# untitled.net
KiCad netlist of a schematic drawn in EAGLE
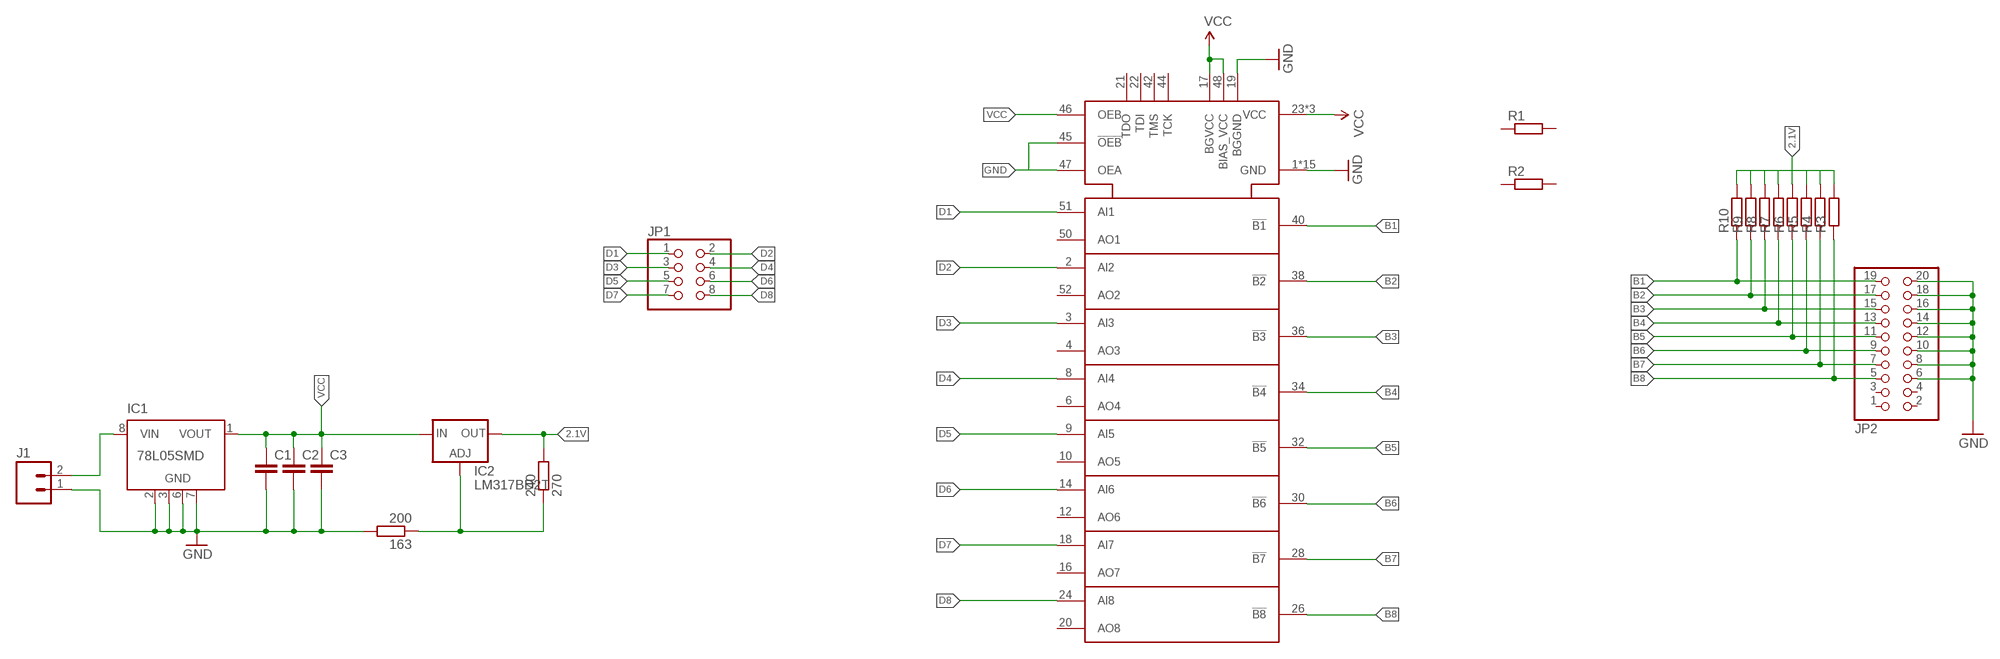
[diagram p0: schematic, sheet 1]

(export (version "E")
  (design (tool "Eeschema 10.0.6"))
  (components
    (comp (ref "163")
      (value "200")
      (footprint "eagle-import:R0805")
      (libsource (lib "eagle-import") (part "R0805"))
    )
    (comp (ref "240")
      (value "270")
      (footprint "eagle-import:R0805")
      (libsource (lib "eagle-import") (part "R0805"))
    )
    (comp (ref "C1")
      (value "CC0805")
      (footprint "eagle-import:C0805")
      (libsource (lib "eagle-import") (part "CC0805"))
    )
    (comp (ref "C2")
      (value "CC0805")
      (footprint "eagle-import:C0805")
      (libsource (lib "eagle-import") (part "CC0805"))
    )
    (comp (ref "C3")
      (value "CC0805")
      (footprint "eagle-import:C0805")
      (libsource (lib "eagle-import") (part "CC0805"))
    )
    (comp (ref "IC1")
      (value "78L05SMD")
      (footprint "eagle-import:SO08")
      (libsource (lib "eagle-import") (part "78LSMD05"))
    )
    (comp (ref "IC2")
      (value "LM317BD2T")
      (footprint "eagle-import:D2PACK")
      (libsource (lib "eagle-import") (part "LM317?BD2T"))
    )
    (comp (ref "J1")
      (value "M02LOCK_LONGPADS")
      (footprint "eagle-import:1X02_LOCK_LONGPADS")
      (libsource (lib "eagle-import") (part "M02LOCK_LONGPADS"))
    )
    (comp (ref "JP1")
      (value "PINHD-2X04_2.54-SMD")
      (footprint "eagle-import:2X04SMD")
      (libsource (lib "eagle-import") (part "PINHD-2X04_2.54-SMD"))
    )
    (comp (ref "JP2")
      (value "PINHD-2X10_2.54-SMD")
      (footprint "eagle-import:2X10SMD")
      (libsource (lib "eagle-import") (part "PINHD-2X10_2.54-SMD"))
    )
    (comp (ref "R1")
      (value "R0805")
      (footprint "eagle-import:R0805")
      (libsource (lib "eagle-import") (part "R0805"))
    )
    (comp (ref "R2")
      (value "R0805")
      (footprint "eagle-import:R0805")
      (libsource (lib "eagle-import") (part "R0805"))
    )
    (comp (ref "R3")
      (value "R0805")
      (footprint "eagle-import:R0805")
      (libsource (lib "eagle-import") (part "R0805"))
    )
    (comp (ref "R4")
      (value "R0805")
      (footprint "eagle-import:R0805")
      (libsource (lib "eagle-import") (part "R0805"))
    )
    (comp (ref "R5")
      (value "R0805")
      (footprint "eagle-import:R0805")
      (libsource (lib "eagle-import") (part "R0805"))
    )
    (comp (ref "R6")
      (value "R0805")
      (footprint "eagle-import:R0805")
      (libsource (lib "eagle-import") (part "R0805"))
    )
    (comp (ref "R7")
      (value "R0805")
      (footprint "eagle-import:R0805")
      (libsource (lib "eagle-import") (part "R0805"))
    )
    (comp (ref "R8")
      (value "R0805")
      (footprint "eagle-import:R0805")
      (libsource (lib "eagle-import") (part "R0805"))
    )
    (comp (ref "R9")
      (value "R0805")
      (footprint "eagle-import:R0805")
      (libsource (lib "eagle-import") (part "R0805"))
    )
    (comp (ref "R10")
      (value "R0805")
      (footprint "eagle-import:R0805")
      (libsource (lib "eagle-import") (part "R0805"))
    )
    (comp (ref "U$1")
      (value "SN74FB2050")
      (footprint "eagle-import:TQFP-10X10-52")
      (libsource (lib "eagle-import") (part "SN74FB2050"))
    )
  )
  (nets
    (net (code "1") (name "2.1V") (class "Default")
      (node (ref "240") (pin "2") (pinfunction "2_2") (pintype "passive"))
      (node (ref "IC2") (pin "2") (pinfunction "OUT_2") (pintype "passive"))
      (node (ref "R10") (pin "2") (pinfunction "2_2") (pintype "passive"))
      (node (ref "R3") (pin "2") (pinfunction "2_2") (pintype "passive"))
      (node (ref "R4") (pin "2") (pinfunction "2_2") (pintype "passive"))
      (node (ref "R5") (pin "2") (pinfunction "2_2") (pintype "passive"))
      (node (ref "R6") (pin "2") (pinfunction "2_2") (pintype "passive"))
      (node (ref "R7") (pin "2") (pinfunction "2_2") (pintype "passive"))
      (node (ref "R8") (pin "2") (pinfunction "2_2") (pintype "passive"))
      (node (ref "R9") (pin "2") (pinfunction "2_2") (pintype "passive"))
    )
    (net (code "2") (name "B1") (class "Default")
      (node (ref "JP2") (pin "19") (pinfunction "19_19") (pintype "passive"))
      (node (ref "R10") (pin "1") (pinfunction "1_1") (pintype "passive"))
      (node (ref "U$1") (pin "40") (pinfunction "~{B1}_40") (pintype "bidirectional"))
    )
    (net (code "3") (name "B2") (class "Default")
      (node (ref "JP2") (pin "17") (pinfunction "17_17") (pintype "passive"))
      (node (ref "R9") (pin "1") (pinfunction "1_1") (pintype "passive"))
      (node (ref "U$1") (pin "38") (pinfunction "~{B2}_38") (pintype "bidirectional"))
    )
    (net (code "4") (name "B3") (class "Default")
      (node (ref "JP2") (pin "15") (pinfunction "15_15") (pintype "passive"))
      (node (ref "R8") (pin "1") (pinfunction "1_1") (pintype "passive"))
      (node (ref "U$1") (pin "36") (pinfunction "~{B3}_36") (pintype "bidirectional"))
    )
    (net (code "5") (name "B4") (class "Default")
      (node (ref "JP2") (pin "13") (pinfunction "13_13") (pintype "passive"))
      (node (ref "R7") (pin "1") (pinfunction "1_1") (pintype "passive"))
      (node (ref "U$1") (pin "34") (pinfunction "~{B4}_34") (pintype "bidirectional"))
    )
    (net (code "6") (name "B5") (class "Default")
      (node (ref "JP2") (pin "11") (pinfunction "11_11") (pintype "passive"))
      (node (ref "R6") (pin "1") (pinfunction "1_1") (pintype "passive"))
      (node (ref "U$1") (pin "32") (pinfunction "~{B5}_32") (pintype "bidirectional"))
    )
    (net (code "7") (name "B6") (class "Default")
      (node (ref "JP2") (pin "9") (pinfunction "9_9") (pintype "passive"))
      (node (ref "R5") (pin "1") (pinfunction "1_1") (pintype "passive"))
      (node (ref "U$1") (pin "30") (pinfunction "~{B6}_30") (pintype "bidirectional"))
    )
    (net (code "8") (name "B7") (class "Default")
      (node (ref "JP2") (pin "7") (pinfunction "7_7") (pintype "passive"))
      (node (ref "R4") (pin "1") (pinfunction "1_1") (pintype "passive"))
      (node (ref "U$1") (pin "28") (pinfunction "~{B7}_28") (pintype "bidirectional"))
    )
    (net (code "9") (name "B8") (class "Default")
      (node (ref "JP2") (pin "5") (pinfunction "5_5") (pintype "passive"))
      (node (ref "R3") (pin "1") (pinfunction "1_1") (pintype "passive"))
      (node (ref "U$1") (pin "26") (pinfunction "~{B8}_26") (pintype "bidirectional"))
    )
    (net (code "10") (name "D1") (class "Default")
      (node (ref "JP1") (pin "1") (pinfunction "1_1") (pintype "passive"))
      (node (ref "U$1") (pin "51") (pinfunction "AI1_51") (pintype "bidirectional"))
    )
    (net (code "11") (name "D2") (class "Default")
      (node (ref "JP1") (pin "2") (pinfunction "2_2") (pintype "passive"))
      (node (ref "U$1") (pin "2") (pinfunction "AI2_2") (pintype "bidirectional"))
    )
    (net (code "12") (name "D3") (class "Default")
      (node (ref "JP1") (pin "3") (pinfunction "3_3") (pintype "passive"))
      (node (ref "U$1") (pin "3") (pinfunction "AI3_3") (pintype "bidirectional"))
    )
    (net (code "13") (name "D4") (class "Default")
      (node (ref "JP1") (pin "4") (pinfunction "4_4") (pintype "passive"))
      (node (ref "U$1") (pin "8") (pinfunction "AI4_8") (pintype "bidirectional"))
    )
    (net (code "14") (name "D5") (class "Default")
      (node (ref "JP1") (pin "5") (pinfunction "5_5") (pintype "passive"))
      (node (ref "U$1") (pin "9") (pinfunction "AI5_9") (pintype "bidirectional"))
    )
    (net (code "15") (name "D6") (class "Default")
      (node (ref "JP1") (pin "6") (pinfunction "6_6") (pintype "passive"))
      (node (ref "U$1") (pin "14") (pinfunction "AI6_14") (pintype "bidirectional"))
    )
    (net (code "16") (name "D7") (class "Default")
      (node (ref "JP1") (pin "7") (pinfunction "7_7") (pintype "passive"))
      (node (ref "U$1") (pin "18") (pinfunction "AI7_18") (pintype "bidirectional"))
    )
    (net (code "17") (name "D8") (class "Default")
      (node (ref "JP1") (pin "8") (pinfunction "8_8") (pintype "passive"))
      (node (ref "U$1") (pin "24") (pinfunction "AI8_24") (pintype "bidirectional"))
    )
    (net (code "18") (name "GND") (class "Default")
      (node (ref "163") (pin "2") (pinfunction "2_2") (pintype "passive"))
      (node (ref "C1") (pin "2") (pinfunction "2_2") (pintype "passive"))
      (node (ref "C2") (pin "2") (pinfunction "2_2") (pintype "passive"))
      (node (ref "C3") (pin "2") (pinfunction "2_2") (pintype "passive"))
      (node (ref "IC1") (pin "2") (pinfunction "GND_2") (pintype "power_in"))
      (node (ref "IC1") (pin "3") (pinfunction "GND_3") (pintype "power_in"))
      (node (ref "IC1") (pin "6") (pinfunction "GND_6") (pintype "power_in"))
      (node (ref "IC1") (pin "7") (pinfunction "GND_7") (pintype "power_in"))
      (node (ref "J1") (pin "1") (pinfunction "1_1") (pintype "passive"))
      (node (ref "JP2") (pin "10") (pinfunction "10_10") (pintype "passive"))
      (node (ref "JP2") (pin "12") (pinfunction "12_12") (pintype "passive"))
      (node (ref "JP2") (pin "14") (pinfunction "14_14") (pintype "passive"))
      (node (ref "JP2") (pin "16") (pinfunction "16_16") (pintype "passive"))
      (node (ref "JP2") (pin "18") (pinfunction "18_18") (pintype "passive"))
      (node (ref "JP2") (pin "20") (pinfunction "20_20") (pintype "passive"))
      (node (ref "JP2") (pin "6") (pinfunction "6_6") (pintype "passive"))
      (node (ref "JP2") (pin "8") (pinfunction "8_8") (pintype "passive"))
      (node (ref "U$1") (pin "1") (pinfunction "GND_1") (pintype "bidirectional"))
      (node (ref "U$1") (pin "11") (pinfunction "GND_11") (pintype "bidirectional"))
      (node (ref "U$1") (pin "13") (pinfunction "GND_13") (pintype "bidirectional"))
      (node (ref "U$1") (pin "15") (pinfunction "GND_15") (pintype "bidirectional"))
      (node (ref "U$1") (pin "19") (pinfunction "BGGND_19") (pintype "bidirectional"))
      (node (ref "U$1") (pin "25") (pinfunction "GND_25") (pintype "bidirectional"))
      (node (ref "U$1") (pin "27") (pinfunction "GND_27") (pintype "bidirectional"))
      (node (ref "U$1") (pin "29") (pinfunction "GND_29") (pintype "bidirectional"))
      (node (ref "U$1") (pin "31") (pinfunction "GND_31") (pintype "bidirectional"))
      (node (ref "U$1") (pin "33") (pinfunction "GND_33") (pintype "bidirectional"))
      (node (ref "U$1") (pin "35") (pinfunction "GND_35") (pintype "bidirectional"))
      (node (ref "U$1") (pin "37") (pinfunction "GND_37") (pintype "bidirectional"))
      (node (ref "U$1") (pin "39") (pinfunction "GND_39") (pintype "bidirectional"))
      (node (ref "U$1") (pin "41") (pinfunction "GND_41") (pintype "bidirectional"))
      (node (ref "U$1") (pin "45") (pinfunction "~{OEB}_45") (pintype "bidirectional"))
      (node (ref "U$1") (pin "47") (pinfunction "OEA_47") (pintype "bidirectional"))
      (node (ref "U$1") (pin "5") (pinfunction "GND_5") (pintype "bidirectional"))
      (node (ref "U$1") (pin "7") (pinfunction "GND_7") (pintype "bidirectional"))
    )
    (net (code "19") (name "Net-(IC1A-VIN)") (class "Default")
      (node (ref "IC1") (pin "8") (pinfunction "VIN_8") (pintype "passive"))
      (node (ref "J1") (pin "2") (pinfunction "2_2") (pintype "passive"))
    )
    (net (code "20") (name "Net-(IC2-ADJ)") (class "Default")
      (node (ref "163") (pin "1") (pinfunction "1_1") (pintype "passive"))
      (node (ref "240") (pin "1") (pinfunction "1_1") (pintype "passive"))
      (node (ref "IC2") (pin "1") (pinfunction "ADJ_1") (pintype "input"))
    )
    (net (code "21") (name "VCC") (class "Default")
      (node (ref "C1") (pin "1") (pinfunction "1_1") (pintype "passive"))
      (node (ref "C2") (pin "1") (pinfunction "1_1") (pintype "passive"))
      (node (ref "C3") (pin "1") (pinfunction "1_1") (pintype "passive"))
      (node (ref "IC1") (pin "1") (pinfunction "VOUT_1") (pintype "output"))
      (node (ref "IC2") (pin "3") (pinfunction "IN_3") (pintype "input"))
      (node (ref "U$1") (pin "17") (pinfunction "BGVCC_17") (pintype "bidirectional"))
      (node (ref "U$1") (pin "23") (pinfunction "VCC_23") (pintype "bidirectional"))
      (node (ref "U$1") (pin "43") (pinfunction "VCC_43") (pintype "bidirectional"))
      (node (ref "U$1") (pin "46") (pinfunction "OEB_46") (pintype "bidirectional"))
      (node (ref "U$1") (pin "48") (pinfunction "BIAS_VCC_48") (pintype "bidirectional"))
      (node (ref "U$1") (pin "49") (pinfunction "VCC_49") (pintype "bidirectional"))
    )
    (net (code "22") (name "unconnected-(JP2-Pad1)") (class "Default")
      (node (ref "JP2") (pin "1") (pinfunction "1_1") (pintype "passive"))
    )
    (net (code "23") (name "unconnected-(JP2-Pad2)") (class "Default")
      (node (ref "JP2") (pin "2") (pinfunction "2_2") (pintype "passive"))
    )
    (net (code "24") (name "unconnected-(JP2-Pad3)") (class "Default")
      (node (ref "JP2") (pin "3") (pinfunction "3_3") (pintype "passive"))
    )
    (net (code "25") (name "unconnected-(JP2-Pad4)") (class "Default")
      (node (ref "JP2") (pin "4") (pinfunction "4_4") (pintype "passive"))
    )
    (net (code "26") (name "unconnected-(R1-Pad1)") (class "Default")
      (node (ref "R1") (pin "1") (pinfunction "1_1") (pintype "passive"))
    )
    (net (code "27") (name "unconnected-(R1-Pad2)") (class "Default")
      (node (ref "R1") (pin "2") (pinfunction "2_2") (pintype "passive"))
    )
    (net (code "28") (name "unconnected-(R2-Pad1)") (class "Default")
      (node (ref "R2") (pin "1") (pinfunction "1_1") (pintype "passive"))
    )
    (net (code "29") (name "unconnected-(R2-Pad2)") (class "Default")
      (node (ref "R2") (pin "2") (pinfunction "2_2") (pintype "passive"))
    )
    (net (code "30") (name "unconnected-(U$1-AO1-Pad50)") (class "Default")
      (node (ref "U$1") (pin "50") (pinfunction "AO1_50") (pintype "bidirectional"))
    )
    (net (code "31") (name "unconnected-(U$1-AO2-Pad52)") (class "Default")
      (node (ref "U$1") (pin "52") (pinfunction "AO2_52") (pintype "bidirectional"))
    )
    (net (code "32") (name "unconnected-(U$1-AO3-Pad4)") (class "Default")
      (node (ref "U$1") (pin "4") (pinfunction "AO3_4") (pintype "bidirectional"))
    )
    (net (code "33") (name "unconnected-(U$1-AO4-Pad6)") (class "Default")
      (node (ref "U$1") (pin "6") (pinfunction "AO4_6") (pintype "bidirectional"))
    )
    (net (code "34") (name "unconnected-(U$1-AO5-Pad10)") (class "Default")
      (node (ref "U$1") (pin "10") (pinfunction "AO5_10") (pintype "bidirectional"))
    )
    (net (code "35") (name "unconnected-(U$1-AO6-Pad12)") (class "Default")
      (node (ref "U$1") (pin "12") (pinfunction "AO6_12") (pintype "bidirectional"))
    )
    (net (code "36") (name "unconnected-(U$1-AO7-Pad16)") (class "Default")
      (node (ref "U$1") (pin "16") (pinfunction "AO7_16") (pintype "bidirectional"))
    )
    (net (code "37") (name "unconnected-(U$1-AO8-Pad20)") (class "Default")
      (node (ref "U$1") (pin "20") (pinfunction "AO8_20") (pintype "bidirectional"))
    )
    (net (code "38") (name "unconnected-(U$1-TCK-Pad44)") (class "Default")
      (node (ref "U$1") (pin "44") (pinfunction "TCK_44") (pintype "bidirectional"))
    )
    (net (code "39") (name "unconnected-(U$1-TDI-Pad22)") (class "Default")
      (node (ref "U$1") (pin "22") (pinfunction "TDI_22") (pintype "bidirectional"))
    )
    (net (code "40") (name "unconnected-(U$1-TDO-Pad21)") (class "Default")
      (node (ref "U$1") (pin "21") (pinfunction "TDO_21") (pintype "bidirectional"))
    )
    (net (code "41") (name "unconnected-(U$1-TMS-Pad42)") (class "Default")
      (node (ref "U$1") (pin "42") (pinfunction "TMS_42") (pintype "bidirectional"))
    )
  )
)
